# electronicload.net
KiCad netlist of a schematic drawn in EAGLE
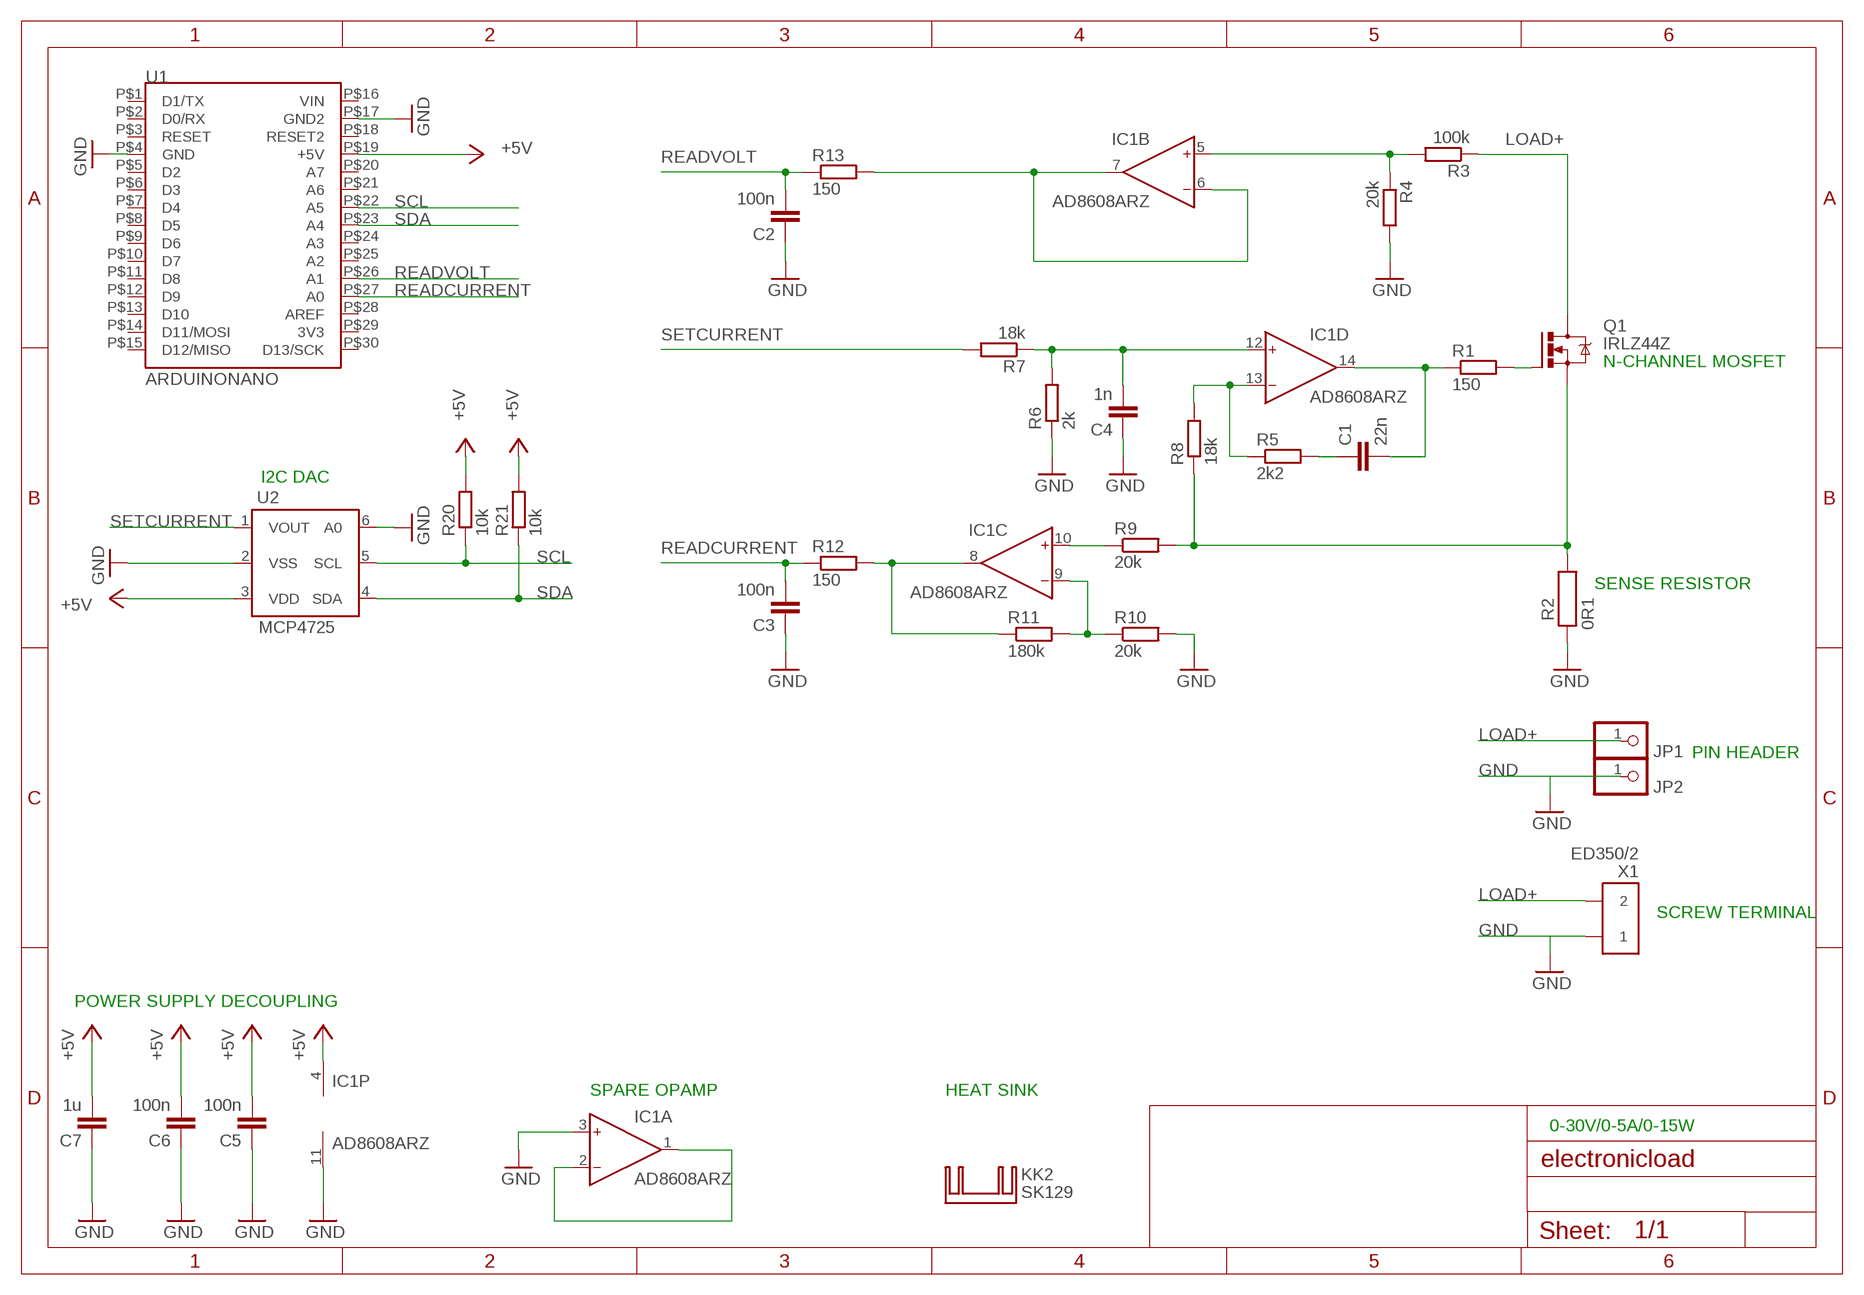
[diagram p0: schematic, sheet 1]

(export (version "E")
  (design (tool "Eeschema 10.0.6"))
  (components
    (comp (ref "C1")
      (value "22n")
      (footprint "eagle-import:C0603K")
      (fields (field (name "TOLERANCE") "10%") (field (name "VOLTAGE") "25V"))
      (libsource (lib "eagle-import") (part "C-EUC0603K"))
    )
    (comp (ref "C2")
      (value "100n")
      (footprint "eagle-import:C0603K")
      (fields (field (name "TOLERANCE") "10%") (field (name "VOLTAGE") "50V"))
      (libsource (lib "eagle-import") (part "C-EUC0603K"))
    )
    (comp (ref "C3")
      (value "100n")
      (footprint "eagle-import:C0603K")
      (fields (field (name "TOLERANCE") "10%") (field (name "VOLTAGE") "50V"))
      (libsource (lib "eagle-import") (part "C-EUC0603K"))
    )
    (comp (ref "C4")
      (value "1n")
      (footprint "eagle-import:C0603K")
      (fields (field (name "TOLERANCE") "10%") (field (name "VOLTAGE") "50V"))
      (libsource (lib "eagle-import") (part "C-EUC0603K"))
    )
    (comp (ref "C5")
      (value "100n")
      (footprint "eagle-import:C0603K")
      (fields (field (name "TOLERANCE") "10%") (field (name "VOLTAGE") "50V"))
      (libsource (lib "eagle-import") (part "C-EUC0603K"))
    )
    (comp (ref "C6")
      (value "100n")
      (footprint "eagle-import:C0603K")
      (fields (field (name "TOLERANCE") "10%") (field (name "VOLTAGE") "50V"))
      (libsource (lib "eagle-import") (part "C-EUC0603K"))
    )
    (comp (ref "C7")
      (value "1u")
      (footprint "eagle-import:C0603K")
      (fields (field (name "TOLERANCE") "10%") (field (name "VOLTAGE") "16V"))
      (libsource (lib "eagle-import") (part "C-EUC0603K"))
    )
    (comp (ref "IC1")
      (value "AD8608ARZ")
      (footprint "eagle-import:SO14")
      (libsource (lib "eagle-import") (part "AD8608R"))
    )
    (comp (ref "JP1")
      (value "PINHD-1X1")
      (footprint "eagle-import:1X01")
      (libsource (lib "eagle-import") (part "PINHD-1X1"))
    )
    (comp (ref "JP2")
      (value "PINHD-1X1")
      (footprint "eagle-import:1X01")
      (libsource (lib "eagle-import") (part "PINHD-1X1"))
    )
    (comp (ref "KK2")
      (value "SK129")
      (footprint "eagle-import:SK129-HOLE")
      (libsource (lib "eagle-import") (part "SK129"))
    )
    (comp (ref "Q1")
      (value "IRLZ44Z")
      (footprint "eagle-import:TO220BV")
      (libsource (lib "eagle-import") (part "IRLZ44Z"))
    )
    (comp (ref "R1")
      (value "150")
      (footprint "eagle-import:R0603")
      (libsource (lib "eagle-import") (part "R-EU_R0603"))
    )
    (comp (ref "R2")
      (value "0R1")
      (footprint "eagle-import:S3")
      (libsource (lib "eagle-import") (part "0R1"))
    )
    (comp (ref "R3")
      (value "100k")
      (footprint "eagle-import:R0603")
      (libsource (lib "eagle-import") (part "R-EU_R0603"))
    )
    (comp (ref "R4")
      (value "20k")
      (footprint "eagle-import:R0603")
      (libsource (lib "eagle-import") (part "R-EU_R0603"))
    )
    (comp (ref "R5")
      (value "2k2")
      (footprint "eagle-import:R0603")
      (libsource (lib "eagle-import") (part "R-EU_R0603"))
    )
    (comp (ref "R6")
      (value "2k")
      (footprint "eagle-import:R0603")
      (libsource (lib "eagle-import") (part "R-EU_R0603"))
    )
    (comp (ref "R7")
      (value "18k")
      (footprint "eagle-import:R0603")
      (libsource (lib "eagle-import") (part "R-EU_R0603"))
    )
    (comp (ref "R8")
      (value "18k")
      (footprint "eagle-import:R0603")
      (libsource (lib "eagle-import") (part "R-EU_R0603"))
    )
    (comp (ref "R9")
      (value "20k")
      (footprint "eagle-import:R0603")
      (libsource (lib "eagle-import") (part "R-EU_R0603"))
    )
    (comp (ref "R10")
      (value "20k")
      (footprint "eagle-import:R0603")
      (libsource (lib "eagle-import") (part "R-EU_R0603"))
    )
    (comp (ref "R11")
      (value "180k")
      (footprint "eagle-import:R0603")
      (libsource (lib "eagle-import") (part "R-EU_R0603"))
    )
    (comp (ref "R12")
      (value "150")
      (footprint "eagle-import:R0603")
      (libsource (lib "eagle-import") (part "R-EU_R0603"))
    )
    (comp (ref "R13")
      (value "150")
      (footprint "eagle-import:R0603")
      (libsource (lib "eagle-import") (part "R-EU_R0603"))
    )
    (comp (ref "R20")
      (value "10k")
      (footprint "eagle-import:R0603")
      (libsource (lib "eagle-import") (part "R-EU_R0603"))
    )
    (comp (ref "R21")
      (value "10k")
      (footprint "eagle-import:R0603")
      (libsource (lib "eagle-import") (part "R-EU_R0603"))
    )
    (comp (ref "U1")
      (value "ARDUINONANO")
      (footprint "eagle-import:ARDUINONANO")
      (libsource (lib "eagle-import") (part "ARDUINONANO"))
    )
    (comp (ref "U2")
      (value "MCP4725")
      (footprint "eagle-import:SOT-23-6")
      (libsource (lib "eagle-import") (part "MCP4725"))
    )
    (comp (ref "X1")
      (value "ED350/2")
      (footprint "eagle-import:ED350_2")
      (libsource (lib "eagle-import") (part "ED350/2"))
    )
  )
  (nets
    (net (code "1") (name "+5V") (class "Default")
      (node (ref "C5") (pin "2") (pinfunction "2_2") (pintype "passive"))
      (node (ref "C6") (pin "2") (pinfunction "2_2") (pintype "passive"))
      (node (ref "C7") (pin "2") (pinfunction "2_2") (pintype "passive"))
      (node (ref "IC1") (pin "4") (pinfunction "V+_4") (pintype "power_in"))
      (node (ref "R20") (pin "2") (pinfunction "2_2") (pintype "passive"))
      (node (ref "R21") (pin "2") (pinfunction "2_2") (pintype "passive"))
      (node (ref "U1") (pin "P$19") (pinfunction "+5V_P$19") (pintype "bidirectional"))
      (node (ref "U2") (pin "3") (pinfunction "VDD_3") (pintype "bidirectional"))
    )
    (net (code "2") (name "/LOAD+") (class "Default")
      (node (ref "JP1") (pin "1") (pinfunction "1_1") (pintype "passive"))
      (node (ref "Q1") (pin "D") (pinfunction "D_D") (pintype "passive"))
      (node (ref "R3") (pin "1") (pinfunction "1_1") (pintype "passive"))
      (node (ref "X1") (pin "P$2") (pinfunction "2_P$2") (pintype "bidirectional"))
    )
    (net (code "3") (name "/READCURRENT") (class "Default")
      (node (ref "C3") (pin "2") (pinfunction "2_2") (pintype "passive"))
      (node (ref "R12") (pin "1") (pinfunction "1_1") (pintype "passive"))
      (node (ref "U1") (pin "P$27") (pinfunction "A0_P$27") (pintype "bidirectional"))
    )
    (net (code "4") (name "/READVOLT") (class "Default")
      (node (ref "C2") (pin "2") (pinfunction "2_2") (pintype "passive"))
      (node (ref "R13") (pin "1") (pinfunction "1_1") (pintype "passive"))
      (node (ref "U1") (pin "P$26") (pinfunction "A1_P$26") (pintype "bidirectional"))
    )
    (net (code "5") (name "/SCL") (class "Default")
      (node (ref "R20") (pin "1") (pinfunction "1_1") (pintype "passive"))
      (node (ref "U1") (pin "P$22") (pinfunction "A5_P$22") (pintype "bidirectional"))
      (node (ref "U2") (pin "5") (pinfunction "SCL_5") (pintype "bidirectional"))
    )
    (net (code "6") (name "/SDA") (class "Default")
      (node (ref "R21") (pin "1") (pinfunction "1_1") (pintype "passive"))
      (node (ref "U1") (pin "P$23") (pinfunction "A4_P$23") (pintype "bidirectional"))
      (node (ref "U2") (pin "4") (pinfunction "SDA_4") (pintype "bidirectional"))
    )
    (net (code "7") (name "/SETCURRENT") (class "Default")
      (node (ref "R7") (pin "2") (pinfunction "2_2") (pintype "passive"))
      (node (ref "U2") (pin "1") (pinfunction "VOUT_1") (pintype "bidirectional"))
    )
    (net (code "8") (name "GND") (class "Default")
      (node (ref "C2") (pin "1") (pinfunction "1_1") (pintype "passive"))
      (node (ref "C3") (pin "1") (pinfunction "1_1") (pintype "passive"))
      (node (ref "C4") (pin "1") (pinfunction "1_1") (pintype "passive"))
      (node (ref "C5") (pin "1") (pinfunction "1_1") (pintype "passive"))
      (node (ref "C6") (pin "1") (pinfunction "1_1") (pintype "passive"))
      (node (ref "C7") (pin "1") (pinfunction "1_1") (pintype "passive"))
      (node (ref "IC1") (pin "11") (pinfunction "V-_11") (pintype "power_in"))
      (node (ref "IC1") (pin "3") (pinfunction "IN+_3") (pintype "input"))
      (node (ref "JP2") (pin "1") (pinfunction "1_1") (pintype "passive"))
      (node (ref "R10") (pin "2") (pinfunction "2_2") (pintype "passive"))
      (node (ref "R2") (pin "1") (pinfunction "1_1") (pintype "bidirectional"))
      (node (ref "R4") (pin "2") (pinfunction "2_2") (pintype "passive"))
      (node (ref "R6") (pin "1") (pinfunction "1_1") (pintype "passive"))
      (node (ref "U1") (pin "P$17") (pinfunction "GND2_P$17") (pintype "bidirectional"))
      (node (ref "U1") (pin "P$4") (pinfunction "GND_P$4") (pintype "bidirectional"))
      (node (ref "U2") (pin "2") (pinfunction "VSS_2") (pintype "bidirectional"))
      (node (ref "U2") (pin "6") (pinfunction "A0_6") (pintype "bidirectional"))
      (node (ref "X1") (pin "P$1") (pinfunction "1_P$1") (pintype "bidirectional"))
    )
    (net (code "9") (name "Net-(C1-Pad1)") (class "Default")
      (node (ref "C1") (pin "1") (pinfunction "1_1") (pintype "passive"))
      (node (ref "R5") (pin "2") (pinfunction "2_2") (pintype "passive"))
    )
    (net (code "10") (name "Net-(IC1A-IN-)") (class "Default")
      (node (ref "IC1") (pin "1") (pinfunction "OUT_1") (pintype "output"))
      (node (ref "IC1") (pin "2") (pinfunction "IN-_2") (pintype "input"))
    )
    (net (code "11") (name "Net-(IC1B-IN+)") (class "Default")
      (node (ref "IC1") (pin "5") (pinfunction "IN+_5") (pintype "input"))
      (node (ref "R3") (pin "2") (pinfunction "2_2") (pintype "passive"))
      (node (ref "R4") (pin "1") (pinfunction "1_1") (pintype "passive"))
    )
    (net (code "12") (name "Net-(IC1B-IN-)") (class "Default")
      (node (ref "IC1") (pin "6") (pinfunction "IN-_6") (pintype "input"))
      (node (ref "IC1") (pin "7") (pinfunction "OUT_7") (pintype "output"))
      (node (ref "R13") (pin "2") (pinfunction "2_2") (pintype "passive"))
    )
    (net (code "13") (name "Net-(IC1C-IN+)") (class "Default")
      (node (ref "IC1") (pin "10") (pinfunction "IN+_10") (pintype "input"))
      (node (ref "R9") (pin "1") (pinfunction "1_1") (pintype "passive"))
    )
    (net (code "14") (name "Net-(IC1C-IN-)") (class "Default")
      (node (ref "IC1") (pin "9") (pinfunction "IN-_9") (pintype "input"))
      (node (ref "R10") (pin "1") (pinfunction "1_1") (pintype "passive"))
      (node (ref "R11") (pin "2") (pinfunction "2_2") (pintype "passive"))
    )
    (net (code "15") (name "Net-(IC1C-OUT)") (class "Default")
      (node (ref "IC1") (pin "8") (pinfunction "OUT_8") (pintype "output"))
      (node (ref "R11") (pin "1") (pinfunction "1_1") (pintype "passive"))
      (node (ref "R12") (pin "2") (pinfunction "2_2") (pintype "passive"))
    )
    (net (code "16") (name "Net-(IC1D-IN+)") (class "Default")
      (node (ref "C4") (pin "2") (pinfunction "2_2") (pintype "passive"))
      (node (ref "IC1") (pin "12") (pinfunction "IN+_12") (pintype "input"))
      (node (ref "R6") (pin "2") (pinfunction "2_2") (pintype "passive"))
      (node (ref "R7") (pin "1") (pinfunction "1_1") (pintype "passive"))
    )
    (net (code "17") (name "Net-(IC1D-IN-)") (class "Default")
      (node (ref "IC1") (pin "13") (pinfunction "IN-_13") (pintype "input"))
      (node (ref "R5") (pin "1") (pinfunction "1_1") (pintype "passive"))
      (node (ref "R8") (pin "2") (pinfunction "2_2") (pintype "passive"))
    )
    (net (code "18") (name "Net-(IC1D-OUT)") (class "Default")
      (node (ref "C1") (pin "2") (pinfunction "2_2") (pintype "passive"))
      (node (ref "IC1") (pin "14") (pinfunction "OUT_14") (pintype "output"))
      (node (ref "R1") (pin "1") (pinfunction "1_1") (pintype "passive"))
    )
    (net (code "19") (name "Net-(Q1-PadG)") (class "Default")
      (node (ref "Q1") (pin "G") (pinfunction "G_G") (pintype "passive"))
      (node (ref "R1") (pin "2") (pinfunction "2_2") (pintype "passive"))
    )
    (net (code "20") (name "Net-(Q1-PadS)") (class "Default")
      (node (ref "Q1") (pin "S") (pinfunction "S_S") (pintype "passive"))
      (node (ref "R2") (pin "2") (pinfunction "2_2") (pintype "bidirectional"))
      (node (ref "R8") (pin "1") (pinfunction "1_1") (pintype "passive"))
      (node (ref "R9") (pin "2") (pinfunction "2_2") (pintype "passive"))
    )
    (net (code "21") (name "unconnected-(U1-3V3-PadP$29)") (class "Default")
      (node (ref "U1") (pin "P$29") (pinfunction "3V3_P$29") (pintype "bidirectional"))
    )
    (net (code "22") (name "unconnected-(U1-A2-PadP$25)") (class "Default")
      (node (ref "U1") (pin "P$25") (pinfunction "A2_P$25") (pintype "bidirectional"))
    )
    (net (code "23") (name "unconnected-(U1-A3-PadP$24)") (class "Default")
      (node (ref "U1") (pin "P$24") (pinfunction "A3_P$24") (pintype "bidirectional"))
    )
    (net (code "24") (name "unconnected-(U1-A6-PadP$21)") (class "Default")
      (node (ref "U1") (pin "P$21") (pinfunction "A6_P$21") (pintype "bidirectional"))
    )
    (net (code "25") (name "unconnected-(U1-A7-PadP$20)") (class "Default")
      (node (ref "U1") (pin "P$20") (pinfunction "A7_P$20") (pintype "bidirectional"))
    )
    (net (code "26") (name "unconnected-(U1-AREF-PadP$28)") (class "Default")
      (node (ref "U1") (pin "P$28") (pinfunction "AREF_P$28") (pintype "bidirectional"))
    )
    (net (code "27") (name "unconnected-(U1-D0{slash}RX-PadP$2)") (class "Default")
      (node (ref "U1") (pin "P$2") (pinfunction "D0/RX_P$2") (pintype "bidirectional"))
    )
    (net (code "28") (name "unconnected-(U1-D1{slash}TX-PadP$1)") (class "Default")
      (node (ref "U1") (pin "P$1") (pinfunction "D1/TX_P$1") (pintype "bidirectional"))
    )
    (net (code "29") (name "unconnected-(U1-D2-PadP$5)") (class "Default")
      (node (ref "U1") (pin "P$5") (pinfunction "D2_P$5") (pintype "bidirectional"))
    )
    (net (code "30") (name "unconnected-(U1-D3-PadP$6)") (class "Default")
      (node (ref "U1") (pin "P$6") (pinfunction "D3_P$6") (pintype "bidirectional"))
    )
    (net (code "31") (name "unconnected-(U1-D4-PadP$7)") (class "Default")
      (node (ref "U1") (pin "P$7") (pinfunction "D4_P$7") (pintype "bidirectional"))
    )
    (net (code "32") (name "unconnected-(U1-D5-PadP$8)") (class "Default")
      (node (ref "U1") (pin "P$8") (pinfunction "D5_P$8") (pintype "bidirectional"))
    )
    (net (code "33") (name "unconnected-(U1-D6-PadP$9)") (class "Default")
      (node (ref "U1") (pin "P$9") (pinfunction "D6_P$9") (pintype "bidirectional"))
    )
    (net (code "34") (name "unconnected-(U1-D7-PadP$10)") (class "Default")
      (node (ref "U1") (pin "P$10") (pinfunction "D7_P$10") (pintype "bidirectional"))
    )
    (net (code "35") (name "unconnected-(U1-D8-PadP$11)") (class "Default")
      (node (ref "U1") (pin "P$11") (pinfunction "D8_P$11") (pintype "bidirectional"))
    )
    (net (code "36") (name "unconnected-(U1-D9-PadP$12)") (class "Default")
      (node (ref "U1") (pin "P$12") (pinfunction "D9_P$12") (pintype "bidirectional"))
    )
    (net (code "37") (name "unconnected-(U1-D10-PadP$13)") (class "Default")
      (node (ref "U1") (pin "P$13") (pinfunction "D10_P$13") (pintype "bidirectional"))
    )
    (net (code "38") (name "unconnected-(U1-D11{slash}MOSI-PadP$14)") (class "Default")
      (node (ref "U1") (pin "P$14") (pinfunction "D11/MOSI_P$14") (pintype "bidirectional"))
    )
    (net (code "39") (name "unconnected-(U1-D12{slash}MISO-PadP$15)") (class "Default")
      (node (ref "U1") (pin "P$15") (pinfunction "D12/MISO_P$15") (pintype "bidirectional"))
    )
    (net (code "40") (name "unconnected-(U1-D13{slash}SCK-PadP$30)") (class "Default")
      (node (ref "U1") (pin "P$30") (pinfunction "D13/SCK_P$30") (pintype "bidirectional"))
    )
    (net (code "41") (name "unconnected-(U1-RESET-PadP$3)") (class "Default")
      (node (ref "U1") (pin "P$3") (pinfunction "RESET_P$3") (pintype "bidirectional"))
    )
    (net (code "42") (name "unconnected-(U1-RESET2-PadP$18)") (class "Default")
      (node (ref "U1") (pin "P$18") (pinfunction "RESET2_P$18") (pintype "bidirectional"))
    )
    (net (code "43") (name "unconnected-(U1-VIN-PadP$16)") (class "Default")
      (node (ref "U1") (pin "P$16") (pinfunction "VIN_P$16") (pintype "bidirectional"))
    )
  )
)
